# PiedPiperSchematic.net
KiCad netlist of a schematic drawn in EAGLE
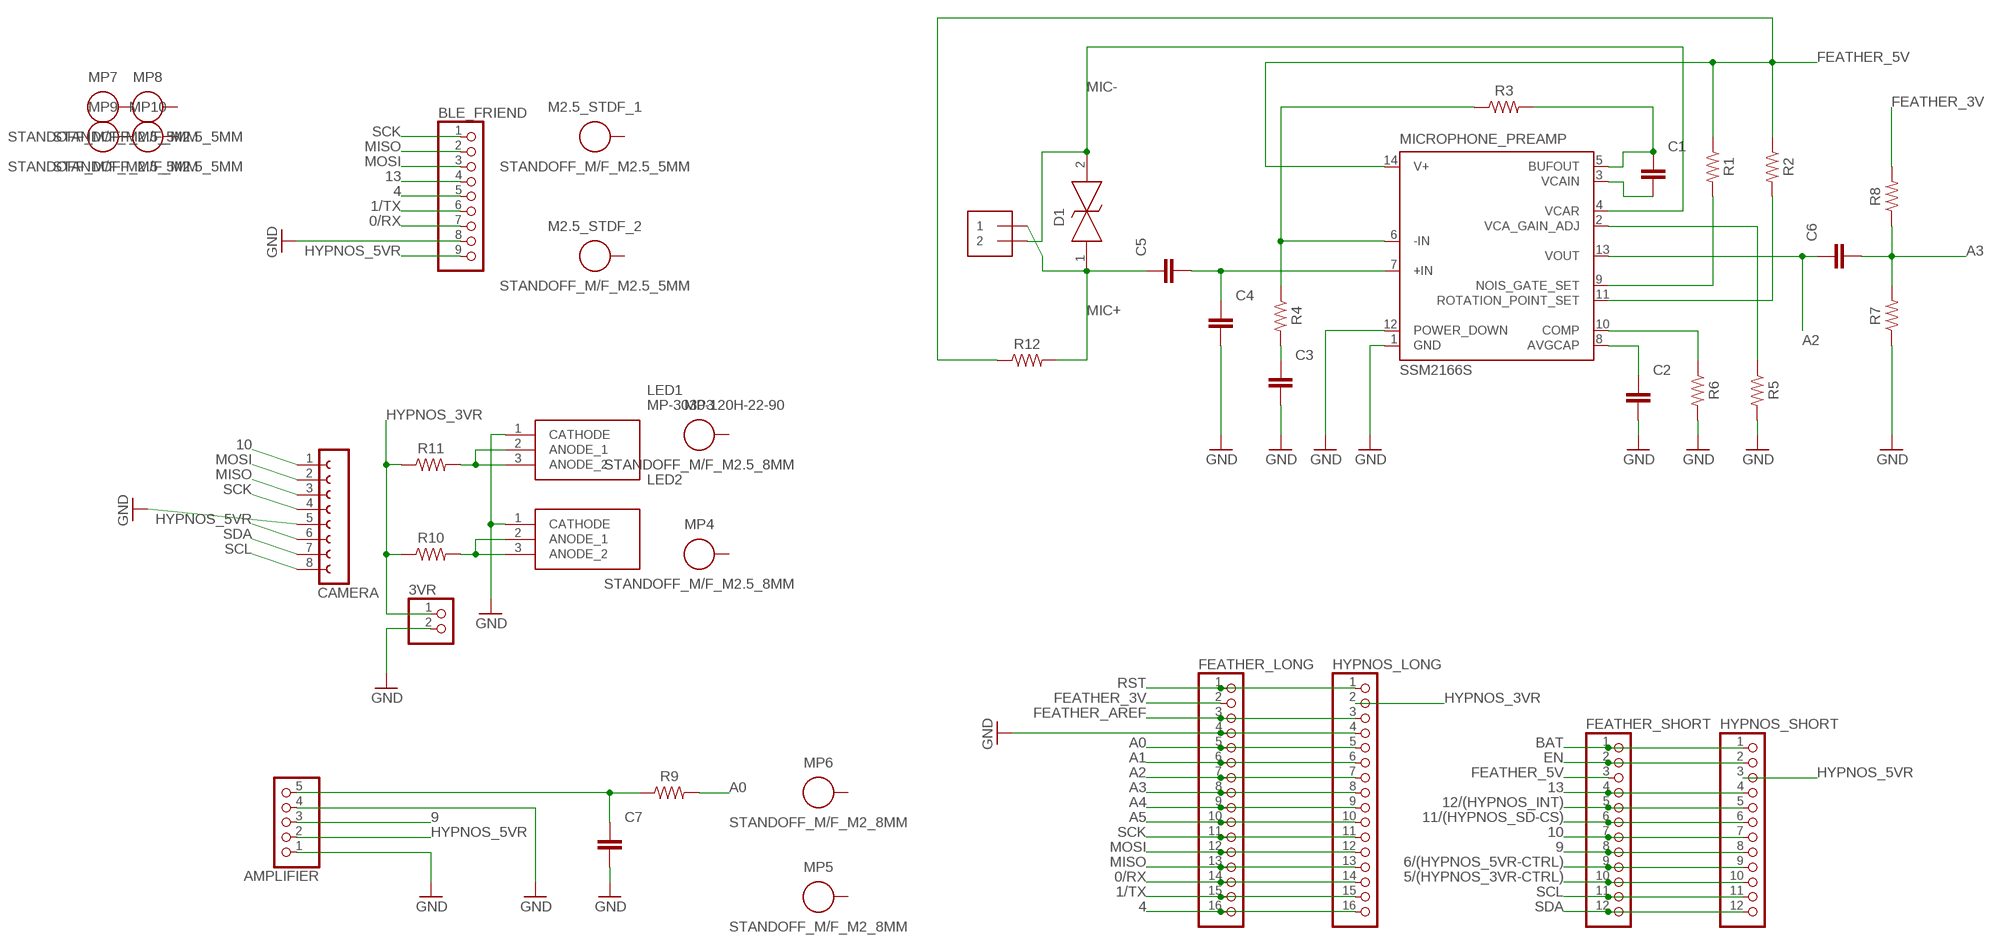
[diagram p0: schematic, sheet 1]

(export (version "E")
  (design (tool "Eeschema 10.0.6"))
  (components
    (comp (ref "3VR")
      (value "PINHD-1X2")
      (footprint "eagle-import:1X02")
      (libsource (lib "eagle-import") (part "PINHD-1X2"))
    )
    (comp (ref "AMPLIFIER")
      (value "PINHD-1X05_2.54-S")
      (footprint "eagle-import:1X05-S")
      (libsource (lib "eagle-import") (part "PINHD-1X05_2.54-S"))
    )
    (comp (ref "BLE_FRIEND")
      (value "PINHD-1X09_2.54-S")
      (footprint "eagle-import:1X09-S")
      (libsource (lib "eagle-import") (part "PINHD-1X09_2.54-S"))
    )
    (comp (ref "C1")
      (value "C_CHIP-0805(2012-METRIC)")
      (footprint "eagle-import:CAPC2012X110")
      (libsource (lib "eagle-import") (part "CCHIP-0805(2012-METRIC)_"))
    )
    (comp (ref "C2")
      (value "C_CHIP-0805(2012-METRIC)")
      (footprint "eagle-import:CAPC2012X110")
      (libsource (lib "eagle-import") (part "CCHIP-0805(2012-METRIC)_"))
    )
    (comp (ref "C3")
      (value "C_CHIP-0805(2012-METRIC)")
      (footprint "eagle-import:CAPC2012X110")
      (libsource (lib "eagle-import") (part "CCHIP-0805(2012-METRIC)_"))
    )
    (comp (ref "C4")
      (value "C_CHIP-0805(2012-METRIC)")
      (footprint "eagle-import:CAPC2012X110")
      (libsource (lib "eagle-import") (part "CCHIP-0805(2012-METRIC)_"))
    )
    (comp (ref "C5")
      (value "C_CHIP-0805(2012-METRIC)")
      (footprint "eagle-import:CAPC2012X110")
      (libsource (lib "eagle-import") (part "CCHIP-0805(2012-METRIC)_"))
    )
    (comp (ref "C6")
      (value "C_CHIP-0805(2012-METRIC)")
      (footprint "eagle-import:CAPC2012X110")
      (libsource (lib "eagle-import") (part "CCHIP-0805(2012-METRIC)_"))
    )
    (comp (ref "C7")
      (value "C_CHIP-0805(2012-METRIC)")
      (footprint "eagle-import:CAPC2012X110")
      (libsource (lib "eagle-import") (part "CCHIP-0805(2012-METRIC)_"))
    )
    (comp (ref "CAMERA")
      (value "FE08W")
      (footprint "eagle-import:FE08W")
      (libsource (lib "eagle-import") (part "FE08W"))
    )
    (comp (ref "D1")
      (value "STS321033B100")
      (footprint "eagle-import:SOD2613X100N")
      (libsource (lib "eagle-import") (part "STS321033B100"))
    )
    (comp (ref "FEATHER_LONG")
      (value "PINHD-1X16_2.54-S")
      (footprint "eagle-import:1X16-S")
      (libsource (lib "eagle-import") (part "PINHD-1X16_2.54-S"))
    )
    (comp (ref "FEATHER_SHORT")
      (value "PINHD-1X12_2.54-S")
      (footprint "eagle-import:1X12-S")
      (libsource (lib "eagle-import") (part "PINHD-1X12_2.54-S"))
    )
    (comp (ref "HYPNOS_LONG")
      (value "PINHD-1X16_2.54-S")
      (footprint "eagle-import:1X16-S")
      (libsource (lib "eagle-import") (part "PINHD-1X16_2.54-S"))
    )
    (comp (ref "HYPNOS_SHORT")
      (value "PINHD-1X12_2.54-S")
      (footprint "eagle-import:1X12-S")
      (libsource (lib "eagle-import") (part "PINHD-1X12_2.54-S"))
    )
    (comp (ref "LED1")
      (value "MP-3030-120H-22-90")
      (footprint "eagle-import:MP3030120H2290")
      (fields (field (name "MOUSER_PART_NUMBER") "896-MP303012H2290"))
      (libsource (lib "eagle-import") (part "MP-3030-120H-22-90"))
    )
    (comp (ref "LED2")
      (value "MP-3030-120H-22-90")
      (footprint "eagle-import:MP3030120H2290")
      (fields (field (name "MOUSER_PART_NUMBER") "896-MP303012H2290"))
      (libsource (lib "eagle-import") (part "MP-3030-120H-22-90"))
    )
    (comp (ref "M2.5_STDF_1")
      (value "STANDOFF_M/F_M2.5_5MM")
      (footprint "eagle-import:STANDOFF_HEX_MALE-FEMALE_500X500_M2.5X0.45_MTGP755H270")
      (libsource (lib "eagle-import") (part "STANDOFF_M/FM2.5_5MM_"))
    )
    (comp (ref "M2.5_STDF_2")
      (value "STANDOFF_M/F_M2.5_5MM")
      (footprint "eagle-import:STANDOFF_HEX_MALE-FEMALE_500X500_M2.5X0.45_MTGP755H270")
      (libsource (lib "eagle-import") (part "STANDOFF_M/FM2.5_5MM_"))
    )
    (comp (ref "MICROPHONE_PREAMP")
      (value "SSM2166S")
      (footprint "eagle-import:SO14")
      (fields (field (name "MF") "ALTERA CORPORATION") (field (name "MPN") "SSM2166S-REEL"))
      (libsource (lib "eagle-import") (part "SSM2166S"))
    )
    (comp (ref "MIC_INPT")
      (value "1X2-3.5MM")
      (footprint "eagle-import:1X2-3.5MM")
      (libsource (lib "eagle-import") (part "1X2-3.5MM"))
    )
    (comp (ref "MP3")
      (value "STANDOFF_M/F_M2.5_8MM")
      (footprint "eagle-import:STANDOFF_HEX_MALE-FEMALE_500X800_M2.5X0.45_MTGP755H270")
      (libsource (lib "eagle-import") (part "STANDOFF_M/FM2.5_8MM_"))
    )
    (comp (ref "MP4")
      (value "STANDOFF_M/F_M2.5_8MM")
      (footprint "eagle-import:STANDOFF_HEX_MALE-FEMALE_500X800_M2.5X0.45_MTGP755H270")
      (libsource (lib "eagle-import") (part "STANDOFF_M/FM2.5_8MM_"))
    )
    (comp (ref "MP5")
      (value "STANDOFF_M/F_M2_8MM")
      (footprint "eagle-import:STANDOFF_HEX_MALE-FEMALE_400X800_M2X0.4_MTGP600H220")
      (libsource (lib "eagle-import") (part "STANDOFF_M/FM2_8MM_"))
    )
    (comp (ref "MP6")
      (value "STANDOFF_M/F_M2_8MM")
      (footprint "eagle-import:STANDOFF_HEX_MALE-FEMALE_400X800_M2X0.4_MTGP600H220")
      (libsource (lib "eagle-import") (part "STANDOFF_M/FM2_8MM_"))
    )
    (comp (ref "MP7")
      (value "STANDOFF_M/F_M2.5_5MM")
      (footprint "eagle-import:STANDOFF_HEX_MALE-FEMALE_500X500_M2.5X0.45_MTGP755H270")
      (libsource (lib "eagle-import") (part "STANDOFF_M/FM2.5_5MM_"))
    )
    (comp (ref "MP8")
      (value "STANDOFF_M/F_M2.5_5MM")
      (footprint "eagle-import:STANDOFF_HEX_MALE-FEMALE_500X500_M2.5X0.45_MTGP755H270")
      (libsource (lib "eagle-import") (part "STANDOFF_M/FM2.5_5MM_"))
    )
    (comp (ref "MP9")
      (value "STANDOFF_M/F_M2.5_5MM")
      (footprint "eagle-import:STANDOFF_HEX_MALE-FEMALE_500X500_M2.5X0.45_MTGP755H270")
      (libsource (lib "eagle-import") (part "STANDOFF_M/FM2.5_5MM_"))
    )
    (comp (ref "MP10")
      (value "STANDOFF_M/F_M2.5_5MM")
      (footprint "eagle-import:STANDOFF_HEX_MALE-FEMALE_500X500_M2.5X0.45_MTGP755H270")
      (libsource (lib "eagle-import") (part "STANDOFF_M/FM2.5_5MM_"))
    )
    (comp (ref "R1")
      (value "R-US_CHIP-1206(3216-METRIC)")
      (footprint "eagle-import:RESC3216X70")
      (libsource (lib "eagle-import") (part "R-USCHIP-1206(3216-METRIC)_"))
    )
    (comp (ref "R2")
      (value "R-US_CHIP-1206(3216-METRIC)")
      (footprint "eagle-import:RESC3216X70")
      (libsource (lib "eagle-import") (part "R-USCHIP-1206(3216-METRIC)_"))
    )
    (comp (ref "R3")
      (value "R-US_CHIP-1206(3216-METRIC)")
      (footprint "eagle-import:RESC3216X70")
      (libsource (lib "eagle-import") (part "R-USCHIP-1206(3216-METRIC)_"))
    )
    (comp (ref "R4")
      (value "R-US_CHIP-1206(3216-METRIC)")
      (footprint "eagle-import:RESC3216X70")
      (libsource (lib "eagle-import") (part "R-USCHIP-1206(3216-METRIC)_"))
    )
    (comp (ref "R5")
      (value "R-US_CHIP-1206(3216-METRIC)")
      (footprint "eagle-import:RESC3216X70")
      (libsource (lib "eagle-import") (part "R-USCHIP-1206(3216-METRIC)_"))
    )
    (comp (ref "R6")
      (value "R-US_CHIP-1206(3216-METRIC)")
      (footprint "eagle-import:RESC3216X70")
      (libsource (lib "eagle-import") (part "R-USCHIP-1206(3216-METRIC)_"))
    )
    (comp (ref "R7")
      (value "R-US_CHIP-1206(3216-METRIC)")
      (footprint "eagle-import:RESC3216X70")
      (libsource (lib "eagle-import") (part "R-USCHIP-1206(3216-METRIC)_"))
    )
    (comp (ref "R8")
      (value "R-US_CHIP-1206(3216-METRIC)")
      (footprint "eagle-import:RESC3216X70")
      (libsource (lib "eagle-import") (part "R-USCHIP-1206(3216-METRIC)_"))
    )
    (comp (ref "R9")
      (value "R-US_CHIP-1206(3216-METRIC)")
      (footprint "eagle-import:RESC3216X70")
      (libsource (lib "eagle-import") (part "R-USCHIP-1206(3216-METRIC)_"))
    )
    (comp (ref "R10")
      (value "R-US_CHIP-1206(3216-METRIC)")
      (footprint "eagle-import:RESC3216X70")
      (libsource (lib "eagle-import") (part "R-USCHIP-1206(3216-METRIC)_"))
    )
    (comp (ref "R11")
      (value "R-US_CHIP-1206(3216-METRIC)")
      (footprint "eagle-import:RESC3216X70")
      (libsource (lib "eagle-import") (part "R-USCHIP-1206(3216-METRIC)_"))
    )
    (comp (ref "R12")
      (value "R-US_CHIP-1206(3216-METRIC)")
      (footprint "eagle-import:RESC3216X70")
      (libsource (lib "eagle-import") (part "R-USCHIP-1206(3216-METRIC)_"))
    )
  )
  (nets
    (net (code "1") (name "/MIC+") (class "Default")
      (node (ref "C5") (pin "1") (pinfunction "1_1") (pintype "passive"))
      (node (ref "D1") (pin "1") (pinfunction "1_1") (pintype "bidirectional"))
      (node (ref "MIC_INPT") (pin "1") (pinfunction "1_1") (pintype "passive"))
      (node (ref "R12") (pin "2") (pinfunction "2_2") (pintype "passive"))
    )
    (net (code "2") (name "/MIC-") (class "Default")
      (node (ref "D1") (pin "2") (pinfunction "2_2") (pintype "bidirectional"))
      (node (ref "MICROPHONE_PREAMP") (pin "4") (pinfunction "VCAR_4") (pintype "input"))
      (node (ref "MIC_INPT") (pin "2") (pinfunction "2_2") (pintype "passive"))
    )
    (net (code "3") (name "0{slash}RX") (class "Default")
      (node (ref "BLE_FRIEND") (pin "7") (pinfunction "7_7") (pintype "passive"))
      (node (ref "FEATHER_LONG") (pin "14") (pinfunction "14_14") (pintype "passive"))
      (node (ref "HYPNOS_LONG") (pin "14") (pinfunction "14_14") (pintype "passive"))
    )
    (net (code "4") (name "1{slash}TX") (class "Default")
      (node (ref "BLE_FRIEND") (pin "6") (pinfunction "6_6") (pintype "passive"))
      (node (ref "FEATHER_LONG") (pin "15") (pinfunction "15_15") (pintype "passive"))
      (node (ref "HYPNOS_LONG") (pin "15") (pinfunction "15_15") (pintype "passive"))
    )
    (net (code "5") (name "4") (class "Default")
      (node (ref "BLE_FRIEND") (pin "5") (pinfunction "5_5") (pintype "passive"))
      (node (ref "FEATHER_LONG") (pin "16") (pinfunction "16_16") (pintype "passive"))
      (node (ref "HYPNOS_LONG") (pin "16") (pinfunction "16_16") (pintype "passive"))
    )
    (net (code "6") (name "5{slash}(HYPNOS_3VR-CTRL)") (class "Default")
      (node (ref "FEATHER_SHORT") (pin "10") (pinfunction "10_10") (pintype "passive"))
      (node (ref "HYPNOS_SHORT") (pin "10") (pinfunction "10_10") (pintype "passive"))
    )
    (net (code "7") (name "6{slash}(HYPNOS_5VR-CTRL)") (class "Default")
      (node (ref "FEATHER_SHORT") (pin "9") (pinfunction "9_9") (pintype "passive"))
      (node (ref "HYPNOS_SHORT") (pin "9") (pinfunction "9_9") (pintype "passive"))
    )
    (net (code "8") (name "9") (class "Default")
      (node (ref "AMPLIFIER") (pin "3") (pinfunction "3_3") (pintype "passive"))
      (node (ref "FEATHER_SHORT") (pin "8") (pinfunction "8_8") (pintype "passive"))
      (node (ref "HYPNOS_SHORT") (pin "8") (pinfunction "8_8") (pintype "passive"))
    )
    (net (code "9") (name "10") (class "Default")
      (node (ref "CAMERA") (pin "1") (pinfunction "1_1") (pintype "passive"))
      (node (ref "FEATHER_SHORT") (pin "7") (pinfunction "7_7") (pintype "passive"))
      (node (ref "HYPNOS_SHORT") (pin "7") (pinfunction "7_7") (pintype "passive"))
    )
    (net (code "10") (name "11{slash}(HYPNOS_SD-CS)") (class "Default")
      (node (ref "FEATHER_SHORT") (pin "6") (pinfunction "6_6") (pintype "passive"))
      (node (ref "HYPNOS_SHORT") (pin "6") (pinfunction "6_6") (pintype "passive"))
    )
    (net (code "11") (name "12{slash}(HYPNOS_INT)") (class "Default")
      (node (ref "FEATHER_SHORT") (pin "5") (pinfunction "5_5") (pintype "passive"))
      (node (ref "HYPNOS_SHORT") (pin "5") (pinfunction "5_5") (pintype "passive"))
    )
    (net (code "12") (name "13") (class "Default")
      (node (ref "BLE_FRIEND") (pin "4") (pinfunction "4_4") (pintype "passive"))
      (node (ref "FEATHER_SHORT") (pin "4") (pinfunction "4_4") (pintype "passive"))
      (node (ref "HYPNOS_SHORT") (pin "4") (pinfunction "4_4") (pintype "passive"))
    )
    (net (code "13") (name "A0") (class "Default")
      (node (ref "FEATHER_LONG") (pin "5") (pinfunction "5_5") (pintype "passive"))
      (node (ref "HYPNOS_LONG") (pin "5") (pinfunction "5_5") (pintype "passive"))
      (node (ref "R9") (pin "2") (pinfunction "2_2") (pintype "passive"))
    )
    (net (code "14") (name "A1") (class "Default")
      (node (ref "FEATHER_LONG") (pin "6") (pinfunction "6_6") (pintype "passive"))
      (node (ref "HYPNOS_LONG") (pin "6") (pinfunction "6_6") (pintype "passive"))
    )
    (net (code "15") (name "A2") (class "Default")
      (node (ref "C6") (pin "1") (pinfunction "1_1") (pintype "passive"))
      (node (ref "FEATHER_LONG") (pin "7") (pinfunction "7_7") (pintype "passive"))
      (node (ref "HYPNOS_LONG") (pin "7") (pinfunction "7_7") (pintype "passive"))
      (node (ref "MICROPHONE_PREAMP") (pin "13") (pinfunction "VOUT_13") (pintype "output"))
    )
    (net (code "16") (name "A3") (class "Default")
      (node (ref "C6") (pin "2") (pinfunction "2_2") (pintype "passive"))
      (node (ref "FEATHER_LONG") (pin "8") (pinfunction "8_8") (pintype "passive"))
      (node (ref "HYPNOS_LONG") (pin "8") (pinfunction "8_8") (pintype "passive"))
      (node (ref "R7") (pin "2") (pinfunction "2_2") (pintype "passive"))
      (node (ref "R8") (pin "1") (pinfunction "1_1") (pintype "passive"))
    )
    (net (code "17") (name "A4") (class "Default")
      (node (ref "FEATHER_LONG") (pin "9") (pinfunction "9_9") (pintype "passive"))
      (node (ref "HYPNOS_LONG") (pin "9") (pinfunction "9_9") (pintype "passive"))
    )
    (net (code "18") (name "A5") (class "Default")
      (node (ref "FEATHER_LONG") (pin "10") (pinfunction "10_10") (pintype "passive"))
      (node (ref "HYPNOS_LONG") (pin "10") (pinfunction "10_10") (pintype "passive"))
    )
    (net (code "19") (name "BAT") (class "Default")
      (node (ref "FEATHER_SHORT") (pin "1") (pinfunction "1_1") (pintype "passive"))
      (node (ref "HYPNOS_SHORT") (pin "1") (pinfunction "1_1") (pintype "passive"))
    )
    (net (code "20") (name "EN") (class "Default")
      (node (ref "FEATHER_SHORT") (pin "2") (pinfunction "2_2") (pintype "passive"))
      (node (ref "HYPNOS_SHORT") (pin "2") (pinfunction "2_2") (pintype "passive"))
    )
    (net (code "21") (name "FEATHER_3V") (class "Default")
      (node (ref "FEATHER_LONG") (pin "2") (pinfunction "2_2") (pintype "passive"))
      (node (ref "R8") (pin "2") (pinfunction "2_2") (pintype "passive"))
    )
    (net (code "22") (name "FEATHER_5V") (class "Default")
      (node (ref "FEATHER_SHORT") (pin "3") (pinfunction "3_3") (pintype "passive"))
      (node (ref "MICROPHONE_PREAMP") (pin "14") (pinfunction "V+_14") (pintype "power_in"))
      (node (ref "R1") (pin "1") (pinfunction "1_1") (pintype "passive"))
      (node (ref "R12") (pin "1") (pinfunction "1_1") (pintype "passive"))
      (node (ref "R2") (pin "1") (pinfunction "1_1") (pintype "passive"))
    )
    (net (code "23") (name "FEATHER_AREF") (class "Default")
      (node (ref "FEATHER_LONG") (pin "3") (pinfunction "3_3") (pintype "passive"))
      (node (ref "HYPNOS_LONG") (pin "3") (pinfunction "3_3") (pintype "passive"))
    )
    (net (code "24") (name "GND") (class "Default")
      (node (ref "3VR") (pin "2") (pinfunction "2_2") (pintype "passive"))
      (node (ref "AMPLIFIER") (pin "1") (pinfunction "1_1") (pintype "passive"))
      (node (ref "AMPLIFIER") (pin "4") (pinfunction "4_4") (pintype "passive"))
      (node (ref "BLE_FRIEND") (pin "8") (pinfunction "8_8") (pintype "passive"))
      (node (ref "C2") (pin "2") (pinfunction "2_2") (pintype "passive"))
      (node (ref "C3") (pin "2") (pinfunction "2_2") (pintype "passive"))
      (node (ref "C4") (pin "2") (pinfunction "2_2") (pintype "passive"))
      (node (ref "C7") (pin "2") (pinfunction "2_2") (pintype "passive"))
      (node (ref "CAMERA") (pin "5") (pinfunction "5_5") (pintype "passive"))
      (node (ref "FEATHER_LONG") (pin "4") (pinfunction "4_4") (pintype "passive"))
      (node (ref "HYPNOS_LONG") (pin "4") (pinfunction "4_4") (pintype "passive"))
      (node (ref "LED1") (pin "1") (pinfunction "CATHODE_1") (pintype "bidirectional"))
      (node (ref "LED2") (pin "1") (pinfunction "CATHODE_1") (pintype "bidirectional"))
      (node (ref "MICROPHONE_PREAMP") (pin "1") (pinfunction "GND_1") (pintype "power_in"))
      (node (ref "MICROPHONE_PREAMP") (pin "12") (pinfunction "POWER_DOWN_12") (pintype "input"))
      (node (ref "R5") (pin "2") (pinfunction "2_2") (pintype "passive"))
      (node (ref "R6") (pin "2") (pinfunction "2_2") (pintype "passive"))
      (node (ref "R7") (pin "1") (pinfunction "1_1") (pintype "passive"))
    )
    (net (code "25") (name "HYPNOS_3VR") (class "Default")
      (node (ref "3VR") (pin "1") (pinfunction "1_1") (pintype "passive"))
      (node (ref "HYPNOS_LONG") (pin "2") (pinfunction "2_2") (pintype "passive"))
      (node (ref "R10") (pin "1") (pinfunction "1_1") (pintype "passive"))
      (node (ref "R11") (pin "1") (pinfunction "1_1") (pintype "passive"))
    )
    (net (code "26") (name "HYPNOS_5VR") (class "Default")
      (node (ref "AMPLIFIER") (pin "2") (pinfunction "2_2") (pintype "passive"))
      (node (ref "BLE_FRIEND") (pin "9") (pinfunction "9_9") (pintype "passive"))
      (node (ref "CAMERA") (pin "6") (pinfunction "6_6") (pintype "passive"))
      (node (ref "HYPNOS_SHORT") (pin "3") (pinfunction "3_3") (pintype "passive"))
    )
    (net (code "27") (name "MISO") (class "Default")
      (node (ref "BLE_FRIEND") (pin "2") (pinfunction "2_2") (pintype "passive"))
      (node (ref "CAMERA") (pin "3") (pinfunction "3_3") (pintype "passive"))
      (node (ref "FEATHER_LONG") (pin "13") (pinfunction "13_13") (pintype "passive"))
      (node (ref "HYPNOS_LONG") (pin "13") (pinfunction "13_13") (pintype "passive"))
    )
    (net (code "28") (name "MOSI") (class "Default")
      (node (ref "BLE_FRIEND") (pin "3") (pinfunction "3_3") (pintype "passive"))
      (node (ref "CAMERA") (pin "2") (pinfunction "2_2") (pintype "passive"))
      (node (ref "FEATHER_LONG") (pin "12") (pinfunction "12_12") (pintype "passive"))
      (node (ref "HYPNOS_LONG") (pin "12") (pinfunction "12_12") (pintype "passive"))
    )
    (net (code "29") (name "Net-(AMPLIFIER-Pad5)") (class "Default")
      (node (ref "AMPLIFIER") (pin "5") (pinfunction "5_5") (pintype "passive"))
      (node (ref "C7") (pin "1") (pinfunction "1_1") (pintype "passive"))
      (node (ref "R9") (pin "1") (pinfunction "1_1") (pintype "passive"))
    )
    (net (code "30") (name "Net-(C3-Pad1)") (class "Default")
      (node (ref "C3") (pin "1") (pinfunction "1_1") (pintype "passive"))
      (node (ref "R4") (pin "2") (pinfunction "2_2") (pintype "passive"))
    )
    (net (code "31") (name "Net-(LED1-ANODE_1)") (class "Default")
      (node (ref "LED1") (pin "2") (pinfunction "ANODE_1_2") (pintype "bidirectional"))
      (node (ref "LED1") (pin "3") (pinfunction "ANODE_2_3") (pintype "bidirectional"))
      (node (ref "R11") (pin "2") (pinfunction "2_2") (pintype "passive"))
    )
    (net (code "32") (name "Net-(LED2-ANODE_1)") (class "Default")
      (node (ref "LED2") (pin "2") (pinfunction "ANODE_1_2") (pintype "bidirectional"))
      (node (ref "LED2") (pin "3") (pinfunction "ANODE_2_3") (pintype "bidirectional"))
      (node (ref "R10") (pin "2") (pinfunction "2_2") (pintype "passive"))
    )
    (net (code "33") (name "Net-(MICROPHONE_PREAMP-+IN)") (class "Default")
      (node (ref "C4") (pin "1") (pinfunction "1_1") (pintype "passive"))
      (node (ref "C5") (pin "2") (pinfunction "2_2") (pintype "passive"))
      (node (ref "MICROPHONE_PREAMP") (pin "7") (pinfunction "+IN_7") (pintype "input"))
    )
    (net (code "34") (name "Net-(MICROPHONE_PREAMP--IN)") (class "Default")
      (node (ref "MICROPHONE_PREAMP") (pin "6") (pinfunction "-IN_6") (pintype "input"))
      (node (ref "R3") (pin "1") (pinfunction "1_1") (pintype "passive"))
      (node (ref "R4") (pin "1") (pinfunction "1_1") (pintype "passive"))
    )
    (net (code "35") (name "Net-(MICROPHONE_PREAMP-AVGCAP)") (class "Default")
      (node (ref "C2") (pin "1") (pinfunction "1_1") (pintype "passive"))
      (node (ref "MICROPHONE_PREAMP") (pin "8") (pinfunction "AVGCAP_8") (pintype "passive"))
    )
    (net (code "36") (name "Net-(MICROPHONE_PREAMP-BUFOUT)") (class "Default")
      (node (ref "C1") (pin "1") (pinfunction "1_1") (pintype "passive"))
      (node (ref "MICROPHONE_PREAMP") (pin "5") (pinfunction "BUFOUT_5") (pintype "output"))
      (node (ref "R3") (pin "2") (pinfunction "2_2") (pintype "passive"))
    )
    (net (code "37") (name "Net-(MICROPHONE_PREAMP-COMP)") (class "Default")
      (node (ref "MICROPHONE_PREAMP") (pin "10") (pinfunction "COMP_10") (pintype "passive"))
      (node (ref "R6") (pin "1") (pinfunction "1_1") (pintype "passive"))
    )
    (net (code "38") (name "Net-(MICROPHONE_PREAMP-NOIS_GATE_SET)") (class "Default")
      (node (ref "MICROPHONE_PREAMP") (pin "9") (pinfunction "NOIS_GATE_SET_9") (pintype "passive"))
      (node (ref "R1") (pin "2") (pinfunction "2_2") (pintype "passive"))
    )
    (net (code "39") (name "Net-(MICROPHONE_PREAMP-ROTATION_POINT_SET)") (class "Default")
      (node (ref "MICROPHONE_PREAMP") (pin "11") (pinfunction "ROTATION_POINT_SET_11") (pintype "passive"))
      (node (ref "R2") (pin "2") (pinfunction "2_2") (pintype "passive"))
    )
    (net (code "40") (name "Net-(MICROPHONE_PREAMP-VCAIN)") (class "Default")
      (node (ref "C1") (pin "2") (pinfunction "2_2") (pintype "passive"))
      (node (ref "MICROPHONE_PREAMP") (pin "3") (pinfunction "VCAIN_3") (pintype "input"))
    )
    (net (code "41") (name "Net-(MICROPHONE_PREAMP-VCA_GAIN_ADJ)") (class "Default")
      (node (ref "MICROPHONE_PREAMP") (pin "2") (pinfunction "VCA_GAIN_ADJ_2") (pintype "input"))
      (node (ref "R5") (pin "1") (pinfunction "1_1") (pintype "passive"))
    )
    (net (code "42") (name "RST") (class "Default")
      (node (ref "FEATHER_LONG") (pin "1") (pinfunction "1_1") (pintype "passive"))
      (node (ref "HYPNOS_LONG") (pin "1") (pinfunction "1_1") (pintype "passive"))
    )
    (net (code "43") (name "SCK") (class "Default")
      (node (ref "BLE_FRIEND") (pin "1") (pinfunction "1_1") (pintype "passive"))
      (node (ref "CAMERA") (pin "4") (pinfunction "4_4") (pintype "passive"))
      (node (ref "FEATHER_LONG") (pin "11") (pinfunction "11_11") (pintype "passive"))
      (node (ref "HYPNOS_LONG") (pin "11") (pinfunction "11_11") (pintype "passive"))
    )
    (net (code "44") (name "SCL") (class "Default")
      (node (ref "CAMERA") (pin "8") (pinfunction "8_8") (pintype "passive"))
      (node (ref "FEATHER_SHORT") (pin "11") (pinfunction "11_11") (pintype "passive"))
      (node (ref "HYPNOS_SHORT") (pin "11") (pinfunction "11_11") (pintype "passive"))
    )
    (net (code "45") (name "SDA") (class "Default")
      (node (ref "CAMERA") (pin "7") (pinfunction "7_7") (pintype "passive"))
      (node (ref "FEATHER_SHORT") (pin "12") (pinfunction "12_12") (pintype "passive"))
      (node (ref "HYPNOS_SHORT") (pin "12") (pinfunction "12_12") (pintype "passive"))
    )
    (net (code "46") (name "unconnected-(M2.5_STDF_1-P$1-Pad1)") (class "Default")
      (node (ref "M2.5_STDF_1") (pin "1") (pinfunction "P$1_1") (pintype "passive"))
    )
    (net (code "47") (name "unconnected-(M2.5_STDF_2-P$1-Pad1)") (class "Default")
      (node (ref "M2.5_STDF_2") (pin "1") (pinfunction "P$1_1") (pintype "passive"))
    )
    (net (code "48") (name "unconnected-(MP3-P$1-Pad1)") (class "Default")
      (node (ref "MP3") (pin "1") (pinfunction "P$1_1") (pintype "passive"))
    )
    (net (code "49") (name "unconnected-(MP4-P$1-Pad1)") (class "Default")
      (node (ref "MP4") (pin "1") (pinfunction "P$1_1") (pintype "passive"))
    )
    (net (code "50") (name "unconnected-(MP5-P$1-Pad1)") (class "Default")
      (node (ref "MP5") (pin "1") (pinfunction "P$1_1") (pintype "passive"))
    )
    (net (code "51") (name "unconnected-(MP6-P$1-Pad1)") (class "Default")
      (node (ref "MP6") (pin "1") (pinfunction "P$1_1") (pintype "passive"))
    )
    (net (code "52") (name "unconnected-(MP7-P$1-Pad1)") (class "Default")
      (node (ref "MP7") (pin "1") (pinfunction "P$1_1") (pintype "passive"))
    )
    (net (code "53") (name "unconnected-(MP8-P$1-Pad1)") (class "Default")
      (node (ref "MP8") (pin "1") (pinfunction "P$1_1") (pintype "passive"))
    )
    (net (code "54") (name "unconnected-(MP9-P$1-Pad1)") (class "Default")
      (node (ref "MP9") (pin "1") (pinfunction "P$1_1") (pintype "passive"))
    )
    (net (code "55") (name "unconnected-(MP10-P$1-Pad1)") (class "Default")
      (node (ref "MP10") (pin "1") (pinfunction "P$1_1") (pintype "passive"))
    )
  )
)
